# VRef_LP3878_MEZ.net
KiCad netlist of a schematic drawn in Altium Designer
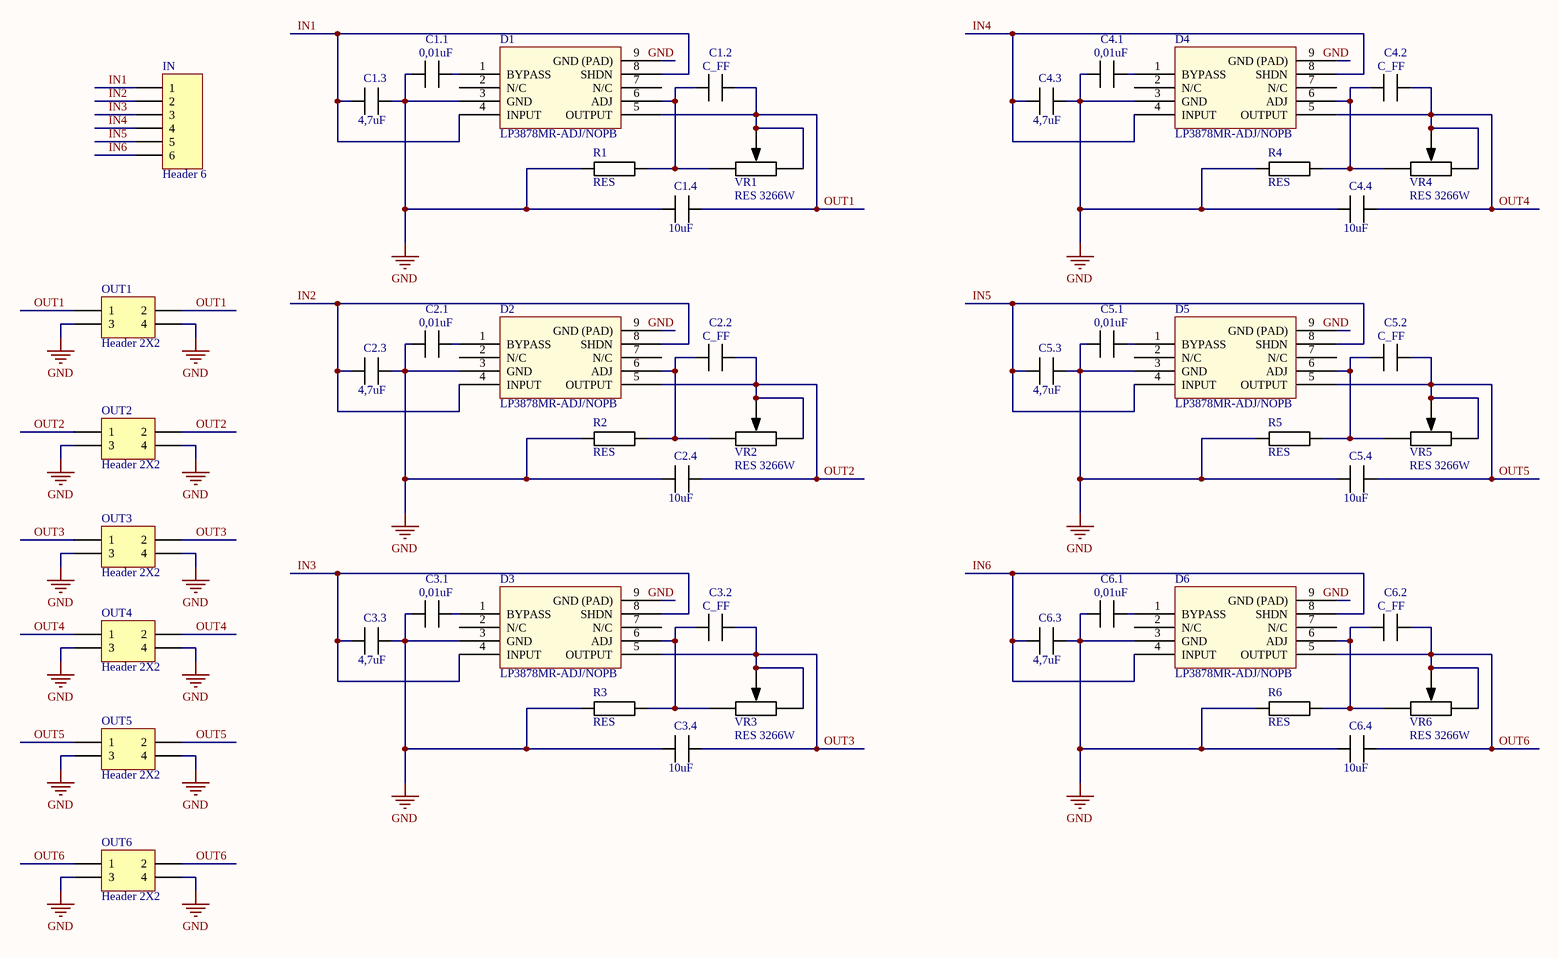
[diagram p0: VRef_LP3878_MEZ.SchDoc]

(export (version "E")
  (design (tool "Eeschema 10.0.6"))
  (components
    (comp (ref "C1.1")
      (value "0,01uF")
      (footprint "aab_Passive:CAP_0603")
      (libsource (lib "aab_Schlib") (part "CAP"))
    )
    (comp (ref "C1.2")
      (value "C_FF")
      (footprint "aab_Passive:CAP_0603")
      (libsource (lib "aab_Schlib") (part "CAP"))
    )
    (comp (ref "C1.3")
      (value "4,7uF")
      (footprint "aab_Passive:CAP_0603")
      (libsource (lib "aab_Schlib") (part "CAP"))
    )
    (comp (ref "C1.4")
      (value "10uF")
      (footprint "aab_Passive:CAP_1812")
      (libsource (lib "aab_Schlib") (part "CAP"))
    )
    (comp (ref "C2.1")
      (value "0,01uF")
      (footprint "aab_Passive:CAP_0603")
      (libsource (lib "aab_Schlib") (part "CAP"))
    )
    (comp (ref "C2.2")
      (value "C_FF")
      (footprint "aab_Passive:CAP_0603")
      (libsource (lib "aab_Schlib") (part "CAP"))
    )
    (comp (ref "C2.3")
      (value "4,7uF")
      (footprint "aab_Passive:CAP_0603")
      (libsource (lib "aab_Schlib") (part "CAP"))
    )
    (comp (ref "C2.4")
      (value "10uF")
      (footprint "aab_Passive:CAP_1812")
      (libsource (lib "aab_Schlib") (part "CAP"))
    )
    (comp (ref "C3.1")
      (value "0,01uF")
      (footprint "aab_Passive:CAP_0603")
      (libsource (lib "aab_Schlib") (part "CAP"))
    )
    (comp (ref "C3.2")
      (value "C_FF")
      (footprint "aab_Passive:CAP_0603")
      (libsource (lib "aab_Schlib") (part "CAP"))
    )
    (comp (ref "C3.3")
      (value "4,7uF")
      (footprint "aab_Passive:CAP_0603")
      (libsource (lib "aab_Schlib") (part "CAP"))
    )
    (comp (ref "C3.4")
      (value "10uF")
      (footprint "aab_Passive:CAP_1812")
      (libsource (lib "aab_Schlib") (part "CAP"))
    )
    (comp (ref "C4.1")
      (value "0,01uF")
      (footprint "aab_Passive:CAP_0603")
      (libsource (lib "aab_Schlib") (part "CAP"))
    )
    (comp (ref "C4.2")
      (value "C_FF")
      (footprint "aab_Passive:CAP_0603")
      (libsource (lib "aab_Schlib") (part "CAP"))
    )
    (comp (ref "C4.3")
      (value "4,7uF")
      (footprint "aab_Passive:CAP_0603")
      (libsource (lib "aab_Schlib") (part "CAP"))
    )
    (comp (ref "C4.4")
      (value "10uF")
      (footprint "aab_Passive:CAP_1812")
      (libsource (lib "aab_Schlib") (part "CAP"))
    )
    (comp (ref "C5.1")
      (value "0,01uF")
      (footprint "aab_Passive:CAP_0603")
      (libsource (lib "aab_Schlib") (part "CAP"))
    )
    (comp (ref "C5.2")
      (value "C_FF")
      (footprint "aab_Passive:CAP_0603")
      (libsource (lib "aab_Schlib") (part "CAP"))
    )
    (comp (ref "C5.3")
      (value "4,7uF")
      (footprint "aab_Passive:CAP_0603")
      (libsource (lib "aab_Schlib") (part "CAP"))
    )
    (comp (ref "C5.4")
      (value "10uF")
      (footprint "aab_Passive:CAP_1812")
      (libsource (lib "aab_Schlib") (part "CAP"))
    )
    (comp (ref "C6.1")
      (value "0,01uF")
      (footprint "aab_Passive:CAP_0603")
      (libsource (lib "aab_Schlib") (part "CAP"))
    )
    (comp (ref "C6.2")
      (value "C_FF")
      (footprint "aab_Passive:CAP_0603")
      (libsource (lib "aab_Schlib") (part "CAP"))
    )
    (comp (ref "C6.3")
      (value "4,7uF")
      (footprint "aab_Passive:CAP_0603")
      (libsource (lib "aab_Schlib") (part "CAP"))
    )
    (comp (ref "C6.4")
      (value "10uF")
      (footprint "aab_Passive:CAP_1812")
      (libsource (lib "aab_Schlib") (part "CAP"))
    )
    (comp (ref "D1")
      (value "LP3878MR-ADJ/NOPB")
      (footprint "aab_Active:LP3878MR-ADJ/NOPB")
      (libsource (lib "aab_Schlib") (part "LP3878MR-ADJ/NOPB"))
    )
    (comp (ref "D2")
      (value "LP3878MR-ADJ/NOPB")
      (footprint "aab_Active:LP3878MR-ADJ/NOPB")
      (libsource (lib "aab_Schlib") (part "LP3878MR-ADJ/NOPB"))
    )
    (comp (ref "D3")
      (value "LP3878MR-ADJ/NOPB")
      (footprint "aab_Active:LP3878MR-ADJ/NOPB")
      (libsource (lib "aab_Schlib") (part "LP3878MR-ADJ/NOPB"))
    )
    (comp (ref "D4")
      (value "LP3878MR-ADJ/NOPB")
      (footprint "aab_Active:LP3878MR-ADJ/NOPB")
      (libsource (lib "aab_Schlib") (part "LP3878MR-ADJ/NOPB"))
    )
    (comp (ref "D5")
      (value "LP3878MR-ADJ/NOPB")
      (footprint "aab_Active:LP3878MR-ADJ/NOPB")
      (libsource (lib "aab_Schlib") (part "LP3878MR-ADJ/NOPB"))
    )
    (comp (ref "D6")
      (value "LP3878MR-ADJ/NOPB")
      (footprint "aab_Active:LP3878MR-ADJ/NOPB")
      (libsource (lib "aab_Schlib") (part "LP3878MR-ADJ/NOPB"))
    )
    (comp (ref "IN")
      (value "Header 6")
      (footprint "HDR1X6")
      (description "Header, 6-Pin")
      (fields (field (name "PUBLISHER") "Altium Limited"))
      (libsource (lib "Miscellaneous Connectors") (part "Header 6"))
    )
    (comp (ref "OUT1")
      (value "Header 2X2")
      (footprint "HDR2X2")
      (description "Header, 2-Pin, Dual row")
      (fields (field (name "PUBLISHER") "Altium Limited"))
      (libsource (lib "Miscellaneous Connectors") (part "Header 2X2"))
    )
    (comp (ref "OUT2")
      (value "Header 2X2")
      (footprint "HDR2X2")
      (description "Header, 2-Pin, Dual row")
      (fields (field (name "PUBLISHER") "Altium Limited"))
      (libsource (lib "Miscellaneous Connectors") (part "Header 2X2"))
    )
    (comp (ref "OUT3")
      (value "Header 2X2")
      (footprint "HDR2X2")
      (description "Header, 2-Pin, Dual row")
      (fields (field (name "PUBLISHER") "Altium Limited"))
      (libsource (lib "Miscellaneous Connectors") (part "Header 2X2"))
    )
    (comp (ref "OUT4")
      (value "Header 2X2")
      (footprint "HDR2X2")
      (description "Header, 2-Pin, Dual row")
      (fields (field (name "PUBLISHER") "Altium Limited"))
      (libsource (lib "Miscellaneous Connectors") (part "Header 2X2"))
    )
    (comp (ref "OUT5")
      (value "Header 2X2")
      (footprint "HDR2X2")
      (description "Header, 2-Pin, Dual row")
      (fields (field (name "PUBLISHER") "Altium Limited"))
      (libsource (lib "Miscellaneous Connectors") (part "Header 2X2"))
    )
    (comp (ref "OUT6")
      (value "Header 2X2")
      (footprint "HDR2X2")
      (description "Header, 2-Pin, Dual row")
      (fields (field (name "PUBLISHER") "Altium Limited"))
      (libsource (lib "Miscellaneous Connectors") (part "Header 2X2"))
    )
    (comp (ref "R1")
      (value "RES")
      (footprint "aab_Passive:RES_0805")
      (libsource (lib "aab_Schlib") (part "RES"))
    )
    (comp (ref "R2")
      (value "RES")
      (footprint "aab_Passive:RES_0805")
      (libsource (lib "aab_Schlib") (part "RES"))
    )
    (comp (ref "R3")
      (value "RES")
      (footprint "aab_Passive:RES_0805")
      (libsource (lib "aab_Schlib") (part "RES"))
    )
    (comp (ref "R4")
      (value "RES")
      (footprint "aab_Passive:RES_0805")
      (libsource (lib "aab_Schlib") (part "RES"))
    )
    (comp (ref "R5")
      (value "RES")
      (footprint "aab_Passive:RES_0805")
      (libsource (lib "aab_Schlib") (part "RES"))
    )
    (comp (ref "R6")
      (value "RES")
      (footprint "aab_Passive:RES_0805")
      (libsource (lib "aab_Schlib") (part "RES"))
    )
    (comp (ref "VR1")
      (value "RES 3266W")
      (footprint "aab_Passive:RES 3266W")
      (libsource (lib "aab_Schlib") (part "RES 3266W"))
    )
    (comp (ref "VR2")
      (value "RES 3266W")
      (footprint "aab_Passive:RES 3266W")
      (libsource (lib "aab_Schlib") (part "RES 3266W"))
    )
    (comp (ref "VR3")
      (value "RES 3266W")
      (footprint "aab_Passive:RES 3266W")
      (libsource (lib "aab_Schlib") (part "RES 3266W"))
    )
    (comp (ref "VR4")
      (value "RES 3266W")
      (footprint "aab_Passive:RES 3266W")
      (libsource (lib "aab_Schlib") (part "RES 3266W"))
    )
    (comp (ref "VR5")
      (value "RES 3266W")
      (footprint "aab_Passive:RES 3266W")
      (libsource (lib "aab_Schlib") (part "RES 3266W"))
    )
    (comp (ref "VR6")
      (value "RES 3266W")
      (footprint "aab_Passive:RES 3266W")
      (libsource (lib "aab_Schlib") (part "RES 3266W"))
    )
  )
  (nets
    (net (code "1") (name "/IN1") (class "Default")
      (node (ref "C1.3") (pin "2") (pinfunction "2_2") (pintype "passive"))
      (node (ref "D1") (pin "4") (pinfunction "INPUT_4") (pintype "passive"))
      (node (ref "D1") (pin "8") (pinfunction "SHDN_8") (pintype "passive"))
      (node (ref "IN") (pin "1") (pinfunction "1_1") (pintype "passive"))
    )
    (net (code "2") (name "/IN2") (class "Default")
      (node (ref "C2.3") (pin "2") (pinfunction "2_2") (pintype "passive"))
      (node (ref "D2") (pin "4") (pinfunction "INPUT_4") (pintype "passive"))
      (node (ref "D2") (pin "8") (pinfunction "SHDN_8") (pintype "passive"))
      (node (ref "IN") (pin "2") (pinfunction "2_2") (pintype "passive"))
    )
    (net (code "3") (name "/IN3") (class "Default")
      (node (ref "C3.3") (pin "2") (pinfunction "2_2") (pintype "passive"))
      (node (ref "D3") (pin "4") (pinfunction "INPUT_4") (pintype "passive"))
      (node (ref "D3") (pin "8") (pinfunction "SHDN_8") (pintype "passive"))
      (node (ref "IN") (pin "3") (pinfunction "3_3") (pintype "passive"))
    )
    (net (code "4") (name "/IN4") (class "Default")
      (node (ref "C4.3") (pin "2") (pinfunction "2_2") (pintype "passive"))
      (node (ref "D4") (pin "4") (pinfunction "INPUT_4") (pintype "passive"))
      (node (ref "D4") (pin "8") (pinfunction "SHDN_8") (pintype "passive"))
      (node (ref "IN") (pin "4") (pinfunction "4_4") (pintype "passive"))
    )
    (net (code "5") (name "/IN5") (class "Default")
      (node (ref "C5.3") (pin "2") (pinfunction "2_2") (pintype "passive"))
      (node (ref "D5") (pin "4") (pinfunction "INPUT_4") (pintype "passive"))
      (node (ref "D5") (pin "8") (pinfunction "SHDN_8") (pintype "passive"))
      (node (ref "IN") (pin "5") (pinfunction "5_5") (pintype "passive"))
    )
    (net (code "6") (name "/IN6") (class "Default")
      (node (ref "C6.3") (pin "2") (pinfunction "2_2") (pintype "passive"))
      (node (ref "D6") (pin "4") (pinfunction "INPUT_4") (pintype "passive"))
      (node (ref "D6") (pin "8") (pinfunction "SHDN_8") (pintype "passive"))
      (node (ref "IN") (pin "6") (pinfunction "6_6") (pintype "passive"))
    )
    (net (code "7") (name "/OUT1") (class "Default")
      (node (ref "C1.2") (pin "1") (pinfunction "1_1") (pintype "passive"))
      (node (ref "C1.4") (pin "1") (pinfunction "1_1") (pintype "passive"))
      (node (ref "D1") (pin "5") (pinfunction "OUTPUT_5") (pintype "passive"))
      (node (ref "OUT1") (pin "1") (pinfunction "1_1") (pintype "passive"))
      (node (ref "OUT1") (pin "2") (pinfunction "2_2") (pintype "passive"))
      (node (ref "VR1") (pin "2") (pinfunction "2_2") (pintype "passive"))
      (node (ref "VR1") (pin "3") (pinfunction "3_3") (pintype "passive"))
    )
    (net (code "8") (name "/OUT2") (class "Default")
      (node (ref "C2.2") (pin "1") (pinfunction "1_1") (pintype "passive"))
      (node (ref "C2.4") (pin "1") (pinfunction "1_1") (pintype "passive"))
      (node (ref "D2") (pin "5") (pinfunction "OUTPUT_5") (pintype "passive"))
      (node (ref "OUT2") (pin "1") (pinfunction "1_1") (pintype "passive"))
      (node (ref "OUT2") (pin "2") (pinfunction "2_2") (pintype "passive"))
      (node (ref "VR2") (pin "2") (pinfunction "2_2") (pintype "passive"))
      (node (ref "VR2") (pin "3") (pinfunction "3_3") (pintype "passive"))
    )
    (net (code "9") (name "/OUT3") (class "Default")
      (node (ref "C3.2") (pin "1") (pinfunction "1_1") (pintype "passive"))
      (node (ref "C3.4") (pin "1") (pinfunction "1_1") (pintype "passive"))
      (node (ref "D3") (pin "5") (pinfunction "OUTPUT_5") (pintype "passive"))
      (node (ref "OUT3") (pin "1") (pinfunction "1_1") (pintype "passive"))
      (node (ref "OUT3") (pin "2") (pinfunction "2_2") (pintype "passive"))
      (node (ref "VR3") (pin "2") (pinfunction "2_2") (pintype "passive"))
      (node (ref "VR3") (pin "3") (pinfunction "3_3") (pintype "passive"))
    )
    (net (code "10") (name "/OUT4") (class "Default")
      (node (ref "C4.2") (pin "1") (pinfunction "1_1") (pintype "passive"))
      (node (ref "C4.4") (pin "1") (pinfunction "1_1") (pintype "passive"))
      (node (ref "D4") (pin "5") (pinfunction "OUTPUT_5") (pintype "passive"))
      (node (ref "OUT4") (pin "1") (pinfunction "1_1") (pintype "passive"))
      (node (ref "OUT4") (pin "2") (pinfunction "2_2") (pintype "passive"))
      (node (ref "VR4") (pin "2") (pinfunction "2_2") (pintype "passive"))
      (node (ref "VR4") (pin "3") (pinfunction "3_3") (pintype "passive"))
    )
    (net (code "11") (name "/OUT5") (class "Default")
      (node (ref "C5.2") (pin "1") (pinfunction "1_1") (pintype "passive"))
      (node (ref "C5.4") (pin "1") (pinfunction "1_1") (pintype "passive"))
      (node (ref "D5") (pin "5") (pinfunction "OUTPUT_5") (pintype "passive"))
      (node (ref "OUT5") (pin "1") (pinfunction "1_1") (pintype "passive"))
      (node (ref "OUT5") (pin "2") (pinfunction "2_2") (pintype "passive"))
      (node (ref "VR5") (pin "2") (pinfunction "2_2") (pintype "passive"))
      (node (ref "VR5") (pin "3") (pinfunction "3_3") (pintype "passive"))
    )
    (net (code "12") (name "/OUT6") (class "Default")
      (node (ref "C6.2") (pin "1") (pinfunction "1_1") (pintype "passive"))
      (node (ref "C6.4") (pin "1") (pinfunction "1_1") (pintype "passive"))
      (node (ref "D6") (pin "5") (pinfunction "OUTPUT_5") (pintype "passive"))
      (node (ref "OUT6") (pin "1") (pinfunction "1_1") (pintype "passive"))
      (node (ref "OUT6") (pin "2") (pinfunction "2_2") (pintype "passive"))
      (node (ref "VR6") (pin "2") (pinfunction "2_2") (pintype "passive"))
      (node (ref "VR6") (pin "3") (pinfunction "3_3") (pintype "passive"))
    )
    (net (code "13") (name "GND") (class "Default")
      (node (ref "C1.1") (pin "2") (pinfunction "2_2") (pintype "passive"))
      (node (ref "C1.3") (pin "1") (pinfunction "1_1") (pintype "passive"))
      (node (ref "C1.4") (pin "2") (pinfunction "2_2") (pintype "passive"))
      (node (ref "C2.1") (pin "2") (pinfunction "2_2") (pintype "passive"))
      (node (ref "C2.3") (pin "1") (pinfunction "1_1") (pintype "passive"))
      (node (ref "C2.4") (pin "2") (pinfunction "2_2") (pintype "passive"))
      (node (ref "C3.1") (pin "2") (pinfunction "2_2") (pintype "passive"))
      (node (ref "C3.3") (pin "1") (pinfunction "1_1") (pintype "passive"))
      (node (ref "C3.4") (pin "2") (pinfunction "2_2") (pintype "passive"))
      (node (ref "C4.1") (pin "2") (pinfunction "2_2") (pintype "passive"))
      (node (ref "C4.3") (pin "1") (pinfunction "1_1") (pintype "passive"))
      (node (ref "C4.4") (pin "2") (pinfunction "2_2") (pintype "passive"))
      (node (ref "C5.1") (pin "2") (pinfunction "2_2") (pintype "passive"))
      (node (ref "C5.3") (pin "1") (pinfunction "1_1") (pintype "passive"))
      (node (ref "C5.4") (pin "2") (pinfunction "2_2") (pintype "passive"))
      (node (ref "C6.1") (pin "2") (pinfunction "2_2") (pintype "passive"))
      (node (ref "C6.3") (pin "1") (pinfunction "1_1") (pintype "passive"))
      (node (ref "C6.4") (pin "2") (pinfunction "2_2") (pintype "passive"))
      (node (ref "D1") (pin "3") (pinfunction "GND_3") (pintype "passive"))
      (node (ref "D1") (pin "9") (pinfunction "GND_(PAD)_9") (pintype "passive"))
      (node (ref "D2") (pin "3") (pinfunction "GND_3") (pintype "passive"))
      (node (ref "D2") (pin "9") (pinfunction "GND_(PAD)_9") (pintype "passive"))
      (node (ref "D3") (pin "3") (pinfunction "GND_3") (pintype "passive"))
      (node (ref "D3") (pin "9") (pinfunction "GND_(PAD)_9") (pintype "passive"))
      (node (ref "D4") (pin "3") (pinfunction "GND_3") (pintype "passive"))
      (node (ref "D4") (pin "9") (pinfunction "GND_(PAD)_9") (pintype "passive"))
      (node (ref "D5") (pin "3") (pinfunction "GND_3") (pintype "passive"))
      (node (ref "D5") (pin "9") (pinfunction "GND_(PAD)_9") (pintype "passive"))
      (node (ref "D6") (pin "3") (pinfunction "GND_3") (pintype "passive"))
      (node (ref "D6") (pin "9") (pinfunction "GND_(PAD)_9") (pintype "passive"))
      (node (ref "OUT1") (pin "3") (pinfunction "3_3") (pintype "passive"))
      (node (ref "OUT1") (pin "4") (pinfunction "4_4") (pintype "passive"))
      (node (ref "OUT2") (pin "3") (pinfunction "3_3") (pintype "passive"))
      (node (ref "OUT2") (pin "4") (pinfunction "4_4") (pintype "passive"))
      (node (ref "OUT3") (pin "3") (pinfunction "3_3") (pintype "passive"))
      (node (ref "OUT3") (pin "4") (pinfunction "4_4") (pintype "passive"))
      (node (ref "OUT4") (pin "3") (pinfunction "3_3") (pintype "passive"))
      (node (ref "OUT4") (pin "4") (pinfunction "4_4") (pintype "passive"))
      (node (ref "OUT5") (pin "3") (pinfunction "3_3") (pintype "passive"))
      (node (ref "OUT5") (pin "4") (pinfunction "4_4") (pintype "passive"))
      (node (ref "OUT6") (pin "3") (pinfunction "3_3") (pintype "passive"))
      (node (ref "OUT6") (pin "4") (pinfunction "4_4") (pintype "passive"))
      (node (ref "R1") (pin "1") (pinfunction "1_1") (pintype "passive"))
      (node (ref "R2") (pin "1") (pinfunction "1_1") (pintype "passive"))
      (node (ref "R3") (pin "1") (pinfunction "1_1") (pintype "passive"))
      (node (ref "R4") (pin "1") (pinfunction "1_1") (pintype "passive"))
      (node (ref "R5") (pin "1") (pinfunction "1_1") (pintype "passive"))
      (node (ref "R6") (pin "1") (pinfunction "1_1") (pintype "passive"))
    )
    (net (code "14") (name "Net-(D1-ADJ)") (class "Default")
      (node (ref "C1.2") (pin "2") (pinfunction "2_2") (pintype "passive"))
      (node (ref "D1") (pin "6") (pinfunction "ADJ_6") (pintype "passive"))
      (node (ref "R1") (pin "2") (pinfunction "2_2") (pintype "passive"))
      (node (ref "VR1") (pin "1") (pinfunction "1_1") (pintype "passive"))
    )
    (net (code "15") (name "Net-(D1-BYPASS)") (class "Default")
      (node (ref "C1.1") (pin "1") (pinfunction "1_1") (pintype "passive"))
      (node (ref "D1") (pin "1") (pinfunction "BYPASS_1") (pintype "passive"))
    )
    (net (code "16") (name "Net-(D2-ADJ)") (class "Default")
      (node (ref "C2.2") (pin "2") (pinfunction "2_2") (pintype "passive"))
      (node (ref "D2") (pin "6") (pinfunction "ADJ_6") (pintype "passive"))
      (node (ref "R2") (pin "2") (pinfunction "2_2") (pintype "passive"))
      (node (ref "VR2") (pin "1") (pinfunction "1_1") (pintype "passive"))
    )
    (net (code "17") (name "Net-(D2-BYPASS)") (class "Default")
      (node (ref "C2.1") (pin "1") (pinfunction "1_1") (pintype "passive"))
      (node (ref "D2") (pin "1") (pinfunction "BYPASS_1") (pintype "passive"))
    )
    (net (code "18") (name "Net-(D3-ADJ)") (class "Default")
      (node (ref "C3.2") (pin "2") (pinfunction "2_2") (pintype "passive"))
      (node (ref "D3") (pin "6") (pinfunction "ADJ_6") (pintype "passive"))
      (node (ref "R3") (pin "2") (pinfunction "2_2") (pintype "passive"))
      (node (ref "VR3") (pin "1") (pinfunction "1_1") (pintype "passive"))
    )
    (net (code "19") (name "Net-(D3-BYPASS)") (class "Default")
      (node (ref "C3.1") (pin "1") (pinfunction "1_1") (pintype "passive"))
      (node (ref "D3") (pin "1") (pinfunction "BYPASS_1") (pintype "passive"))
    )
    (net (code "20") (name "Net-(D4-ADJ)") (class "Default")
      (node (ref "C4.2") (pin "2") (pinfunction "2_2") (pintype "passive"))
      (node (ref "D4") (pin "6") (pinfunction "ADJ_6") (pintype "passive"))
      (node (ref "R4") (pin "2") (pinfunction "2_2") (pintype "passive"))
      (node (ref "VR4") (pin "1") (pinfunction "1_1") (pintype "passive"))
    )
    (net (code "21") (name "Net-(D4-BYPASS)") (class "Default")
      (node (ref "C4.1") (pin "1") (pinfunction "1_1") (pintype "passive"))
      (node (ref "D4") (pin "1") (pinfunction "BYPASS_1") (pintype "passive"))
    )
    (net (code "22") (name "Net-(D5-ADJ)") (class "Default")
      (node (ref "C5.2") (pin "2") (pinfunction "2_2") (pintype "passive"))
      (node (ref "D5") (pin "6") (pinfunction "ADJ_6") (pintype "passive"))
      (node (ref "R5") (pin "2") (pinfunction "2_2") (pintype "passive"))
      (node (ref "VR5") (pin "1") (pinfunction "1_1") (pintype "passive"))
    )
    (net (code "23") (name "Net-(D5-BYPASS)") (class "Default")
      (node (ref "C5.1") (pin "1") (pinfunction "1_1") (pintype "passive"))
      (node (ref "D5") (pin "1") (pinfunction "BYPASS_1") (pintype "passive"))
    )
    (net (code "24") (name "Net-(D6-ADJ)") (class "Default")
      (node (ref "C6.2") (pin "2") (pinfunction "2_2") (pintype "passive"))
      (node (ref "D6") (pin "6") (pinfunction "ADJ_6") (pintype "passive"))
      (node (ref "R6") (pin "2") (pinfunction "2_2") (pintype "passive"))
      (node (ref "VR6") (pin "1") (pinfunction "1_1") (pintype "passive"))
    )
    (net (code "25") (name "Net-(D6-BYPASS)") (class "Default")
      (node (ref "C6.1") (pin "1") (pinfunction "1_1") (pintype "passive"))
      (node (ref "D6") (pin "1") (pinfunction "BYPASS_1") (pintype "passive"))
    )
    (net (code "26") (name "unconnected-(D1-N{slash}C-Pad2)") (class "Default")
      (node (ref "D1") (pin "2") (pinfunction "N/C_2") (pintype "passive"))
    )
    (net (code "27") (name "unconnected-(D1-N{slash}C-Pad7)") (class "Default")
      (node (ref "D1") (pin "7") (pinfunction "N/C_7") (pintype "passive"))
    )
    (net (code "28") (name "unconnected-(D2-N{slash}C-Pad2)") (class "Default")
      (node (ref "D2") (pin "2") (pinfunction "N/C_2") (pintype "passive"))
    )
    (net (code "29") (name "unconnected-(D2-N{slash}C-Pad7)") (class "Default")
      (node (ref "D2") (pin "7") (pinfunction "N/C_7") (pintype "passive"))
    )
    (net (code "30") (name "unconnected-(D3-N{slash}C-Pad2)") (class "Default")
      (node (ref "D3") (pin "2") (pinfunction "N/C_2") (pintype "passive"))
    )
    (net (code "31") (name "unconnected-(D3-N{slash}C-Pad7)") (class "Default")
      (node (ref "D3") (pin "7") (pinfunction "N/C_7") (pintype "passive"))
    )
    (net (code "32") (name "unconnected-(D4-N{slash}C-Pad2)") (class "Default")
      (node (ref "D4") (pin "2") (pinfunction "N/C_2") (pintype "passive"))
    )
    (net (code "33") (name "unconnected-(D4-N{slash}C-Pad7)") (class "Default")
      (node (ref "D4") (pin "7") (pinfunction "N/C_7") (pintype "passive"))
    )
    (net (code "34") (name "unconnected-(D5-N{slash}C-Pad2)") (class "Default")
      (node (ref "D5") (pin "2") (pinfunction "N/C_2") (pintype "passive"))
    )
    (net (code "35") (name "unconnected-(D5-N{slash}C-Pad7)") (class "Default")
      (node (ref "D5") (pin "7") (pinfunction "N/C_7") (pintype "passive"))
    )
    (net (code "36") (name "unconnected-(D6-N{slash}C-Pad2)") (class "Default")
      (node (ref "D6") (pin "2") (pinfunction "N/C_2") (pintype "passive"))
    )
    (net (code "37") (name "unconnected-(D6-N{slash}C-Pad7)") (class "Default")
      (node (ref "D6") (pin "7") (pinfunction "N/C_7") (pintype "passive"))
    )
  )
)
